# OpenSpindle_BASE.net
KiCad netlist of a schematic drawn in EAGLE
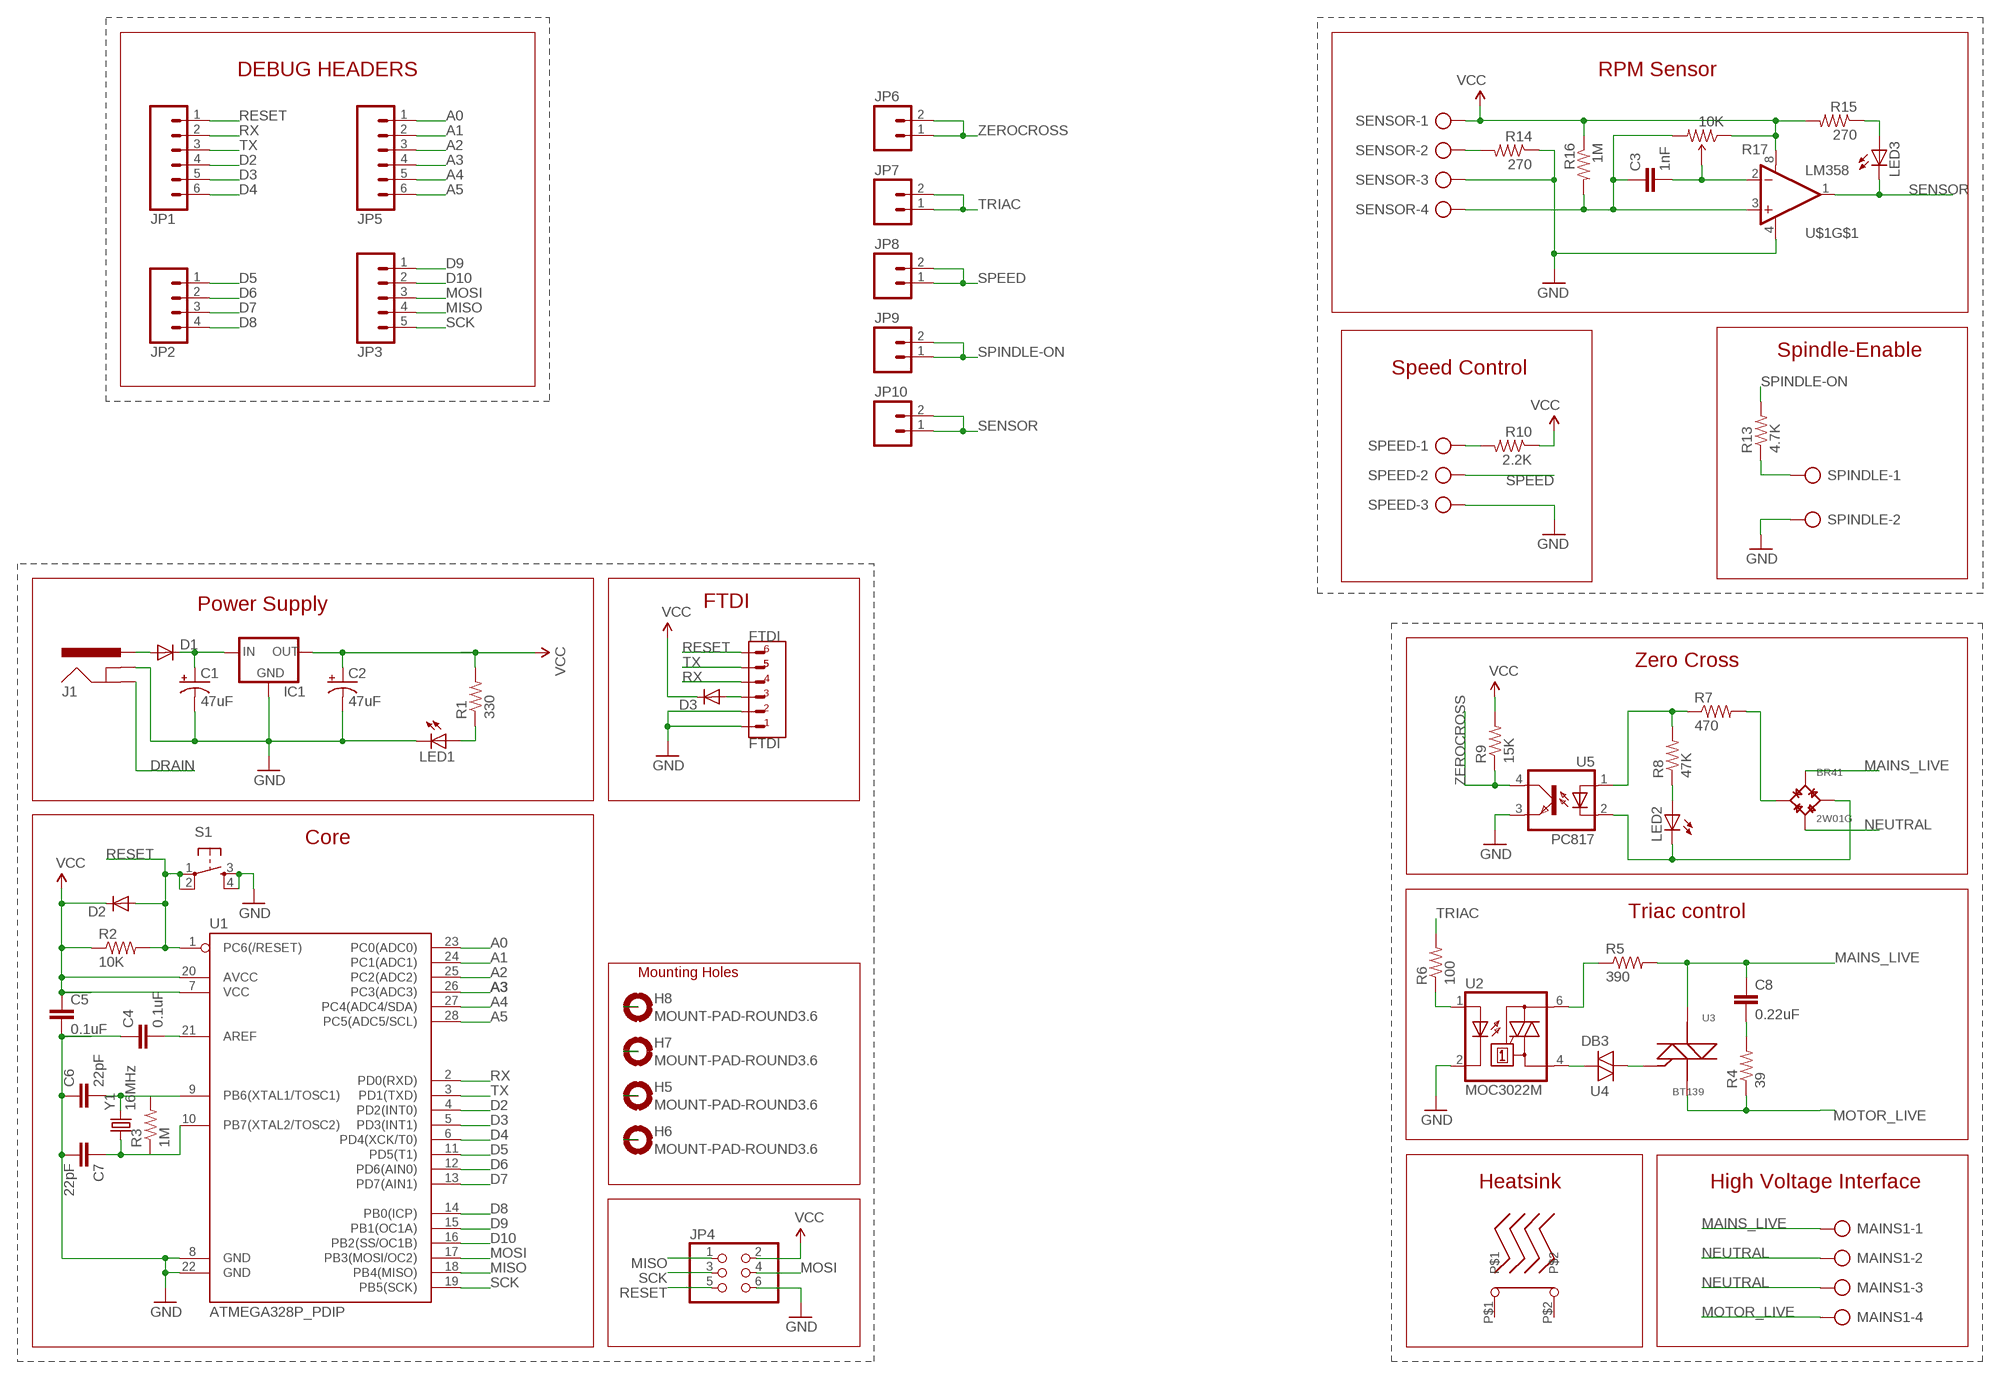
[diagram p0: schematic, sheet 1]

(export (version "E")
  (design (tool "Eeschema 10.0.6"))
  (components
    (comp (ref "BR41")
      (value "2W01G")
      (footprint "eagle-import:DIODEBRIDGE")
      (libsource (lib "eagle-import") (part "DIODEBRIDGE"))
    )
    (comp (ref "C1")
      (value "47uF")
      (footprint "eagle-import:CPOL-RADIAL-10UF-25V")
      (libsource (lib "eagle-import") (part "CAP_POLPTH2"))
    )
    (comp (ref "C2")
      (value "47uF")
      (footprint "eagle-import:CPOL-RADIAL-10UF-25V")
      (libsource (lib "eagle-import") (part "CAP_POLPTH2"))
    )
    (comp (ref "C3")
      (value "1nF")
      (footprint "eagle-import:CAP-PTH-SMALL")
      (libsource (lib "eagle-import") (part "SparkFun-Capacitors_CAPPTH"))
    )
    (comp (ref "C4")
      (value "0.1uF")
      (footprint "eagle-import:CAP-PTH-SMALL")
      (libsource (lib "eagle-import") (part "SparkFun-Capacitors_CAPPTH"))
    )
    (comp (ref "C5")
      (value "0.1uF")
      (footprint "eagle-import:CAP-PTH-SMALL")
      (libsource (lib "eagle-import") (part "SparkFun-Capacitors_CAPPTH"))
    )
    (comp (ref "C6")
      (value "22pF")
      (footprint "eagle-import:CAP-PTH-SMALL")
      (libsource (lib "eagle-import") (part "SparkFun-Capacitors_CAPPTH"))
    )
    (comp (ref "C7")
      (value "22pF")
      (footprint "eagle-import:CAP-PTH-SMALL")
      (libsource (lib "eagle-import") (part "SparkFun-Capacitors_CAPPTH"))
    )
    (comp (ref "C8")
      (value "0.22uF")
      (footprint "eagle-import:CAP-PTH-SMALL")
      (libsource (lib "eagle-import") (part "CAPPTH"))
    )
    (comp (ref "D1")
      (value "DIODEPTH")
      (footprint "eagle-import:DIODE-1N4001")
      (libsource (lib "eagle-import") (part "DIODEPTH"))
    )
    (comp (ref "D2")
      (value "DIODEPTH")
      (footprint "eagle-import:DIODE-1N4001")
      (libsource (lib "eagle-import") (part "DIODEPTH"))
    )
    (comp (ref "D3")
      (value "DIODEPTH")
      (footprint "eagle-import:DIODE-1N4001")
      (libsource (lib "eagle-import") (part "DIODEPTH"))
    )
    (comp (ref "FTDI")
      (value "FTDI")
      (footprint "eagle-import:6PINHEADER")
      (libsource (lib "eagle-import") (part "6PINHEADER0.1{dblquote}"))
    )
    (comp (ref "H5")
      (value "MOUNT-PAD-ROUND3.6")
      (footprint "eagle-import:3,6-PAD")
      (libsource (lib "eagle-import") (part "MOUNT-PAD-ROUND3.6"))
    )
    (comp (ref "H6")
      (value "MOUNT-PAD-ROUND3.6")
      (footprint "eagle-import:3,6-PAD")
      (libsource (lib "eagle-import") (part "MOUNT-PAD-ROUND3.6"))
    )
    (comp (ref "H7")
      (value "MOUNT-PAD-ROUND3.6")
      (footprint "eagle-import:3,6-PAD")
      (libsource (lib "eagle-import") (part "MOUNT-PAD-ROUND3.6"))
    )
    (comp (ref "H8")
      (value "MOUNT-PAD-ROUND3.6")
      (footprint "eagle-import:3,6-PAD")
      (libsource (lib "eagle-import") (part "MOUNT-PAD-ROUND3.6"))
    )
    (comp (ref "IC1")
      (value "V_REG_78XX-TO-220")
      (footprint "eagle-import:TO-220-ALT")
      (libsource (lib "eagle-import") (part "V_REG_78XX-TO-220"))
    )
    (comp (ref "J1")
      (value "POWER_JACKPTH_LOCK")
      (footprint "eagle-import:POWER_JACK_PTH_LOCK")
      (libsource (lib "eagle-import") (part "POWER_JACKPTH_LOCK"))
    )
    (comp (ref "JP1")
      (value "M06LOCK")
      (footprint "eagle-import:1X06_LOCK")
      (libsource (lib "eagle-import") (part "M06LOCK"))
    )
    (comp (ref "JP2")
      (value "M04LOCK")
      (footprint "eagle-import:1X04_LOCK")
      (libsource (lib "eagle-import") (part "M04LOCK"))
    )
    (comp (ref "JP3")
      (value "M05LOCK")
      (footprint "eagle-import:1X05_LOCK")
      (libsource (lib "eagle-import") (part "M05LOCK"))
    )
    (comp (ref "JP4")
      (value "PINHD-2X3")
      (footprint "eagle-import:2X03")
      (libsource (lib "eagle-import") (part "PINHD-2X3"))
    )
    (comp (ref "JP5")
      (value "M06LOCK")
      (footprint "eagle-import:1X06_LOCK")
      (libsource (lib "eagle-import") (part "M06LOCK"))
    )
    (comp (ref "JP6")
      (value "M02LOCK")
      (footprint "eagle-import:1X02_LOCK")
      (libsource (lib "eagle-import") (part "M02LOCK"))
    )
    (comp (ref "JP7")
      (value "M02LOCK")
      (footprint "eagle-import:1X02_LOCK")
      (libsource (lib "eagle-import") (part "M02LOCK"))
    )
    (comp (ref "JP8")
      (value "M02LOCK")
      (footprint "eagle-import:1X02_LOCK")
      (libsource (lib "eagle-import") (part "M02LOCK"))
    )
    (comp (ref "JP9")
      (value "M02LOCK")
      (footprint "eagle-import:1X02_LOCK")
      (libsource (lib "eagle-import") (part "M02LOCK"))
    )
    (comp (ref "JP10")
      (value "M02LOCK")
      (footprint "eagle-import:1X02_LOCK")
      (libsource (lib "eagle-import") (part "M02LOCK"))
    )
    (comp (ref "LED1")
      (value "LED5MM")
      (footprint "eagle-import:LED5MM")
      (libsource (lib "eagle-import") (part "adafruit2012_LED5MM"))
    )
    (comp (ref "LED2")
      (value "LED5MM")
      (footprint "eagle-import:LED5MM")
      (libsource (lib "eagle-import") (part "LED5MM"))
    )
    (comp (ref "LED3")
      (value "LED5MM")
      (footprint "eagle-import:LED5MM")
      (libsource (lib "eagle-import") (part "adafruit2012_LED5MM"))
    )
    (comp (ref "MAINS1")
      (value "AK500/4")
      (footprint "eagle-import:AK500_4")
      (libsource (lib "eagle-import") (part "AK500/4"))
    )
    (comp (ref "R1")
      (value "330")
      (footprint "eagle-import:AXIAL-0.3")
      (libsource (lib "eagle-import") (part "RESISTORAXIAL-0.3"))
    )
    (comp (ref "R2")
      (value "10K")
      (footprint "eagle-import:AXIAL-0.3")
      (libsource (lib "eagle-import") (part "RESISTORAXIAL-0.3"))
    )
    (comp (ref "R3")
      (value "1M")
      (footprint "eagle-import:AXIAL-0.3")
      (libsource (lib "eagle-import") (part "RESISTORAXIAL-0.3"))
    )
    (comp (ref "R4")
      (value "39")
      (footprint "eagle-import:AXIAL-0.3")
      (libsource (lib "eagle-import") (part "RESISTORAXIAL-0.3"))
    )
    (comp (ref "R5")
      (value "390")
      (footprint "eagle-import:AXIAL-0.3")
      (libsource (lib "eagle-import") (part "RESISTORAXIAL-0.3"))
    )
    (comp (ref "R6")
      (value "100")
      (footprint "eagle-import:AXIAL-0.3")
      (libsource (lib "eagle-import") (part "RESISTORAXIAL-0.3"))
    )
    (comp (ref "R7")
      (value "470")
      (footprint "eagle-import:SQM_5-10")
      (libsource (lib "eagle-import") (part "RESISTORM_5-10"))
    )
    (comp (ref "R8")
      (value "47K")
      (footprint "eagle-import:SQM_5-10")
      (libsource (lib "eagle-import") (part "RESISTORM_5-10"))
    )
    (comp (ref "R9")
      (value "15K")
      (footprint "eagle-import:AXIAL-0.3")
      (libsource (lib "eagle-import") (part "RESISTORAXIAL-0.3"))
    )
    (comp (ref "R10")
      (value "2.2K")
      (footprint "eagle-import:AXIAL-0.3")
      (libsource (lib "eagle-import") (part "RESISTORAXIAL-0.3"))
    )
    (comp (ref "R13")
      (value "4.7K")
      (footprint "eagle-import:AXIAL-0.3")
      (libsource (lib "eagle-import") (part "RESISTORAXIAL-0.3"))
    )
    (comp (ref "R14")
      (value "270")
      (footprint "eagle-import:AXIAL-0.3")
      (libsource (lib "eagle-import") (part "RESISTORAXIAL-0.3"))
    )
    (comp (ref "R15")
      (value "270")
      (footprint "eagle-import:AXIAL-0.3")
      (libsource (lib "eagle-import") (part "RESISTORAXIAL-0.3"))
    )
    (comp (ref "R16")
      (value "1M")
      (footprint "eagle-import:AXIAL-0.3")
      (libsource (lib "eagle-import") (part "RESISTORAXIAL-0.3"))
    )
    (comp (ref "R17")
      (value "10K")
      (footprint "eagle-import:TRIMPOT_PTH_S3_LOCK")
      (libsource (lib "eagle-import") (part "TRIMPOTTRIMPOT_PTH_S3_LOCK"))
    )
    (comp (ref "S1")
      (value "TAC_SWITCHPTH")
      (footprint "eagle-import:TACTILE-PTH")
      (libsource (lib "eagle-import") (part "TAC_SWITCHPTH"))
    )
    (comp (ref "SENSOR")
      (value "AK500/4")
      (footprint "eagle-import:AK500_4")
      (libsource (lib "eagle-import") (part "AK500/4"))
    )
    (comp (ref "SPEED")
      (value "AK500/3")
      (footprint "eagle-import:AK500_3")
      (libsource (lib "eagle-import") (part "AK500/3"))
    )
    (comp (ref "SPINDLE")
      (value "AK500/2")
      (footprint "eagle-import:AK500_2")
      (libsource (lib "eagle-import") (part "AK500/2"))
    )
    (comp (ref "U$1")
      (value "LM358")
      (footprint "eagle-import:DIP08")
      (libsource (lib "eagle-import") (part "LM358"))
    )
    (comp (ref "U$2")
      (value "HEATSINK529802B02500G")
      (footprint "eagle-import:529802B02500G")
      (libsource (lib "eagle-import") (part "HEATSINK529802B02500G"))
    )
    (comp (ref "U1")
      (value "ATMEGA328P_PDIP")
      (footprint "eagle-import:DIL28-3")
      (libsource (lib "eagle-import") (part "ATMEGA328P_PDIP"))
    )
    (comp (ref "U2")
      (value "MOC3022M")
      (footprint "eagle-import:DIL06")
      (fields (field (name "MF") "FAIRCHILD SEMICONDUCTOR") (field (name "MPN") "MOC3022-M"))
      (libsource (lib "eagle-import") (part "MOC30M22"))
    )
    (comp (ref "U3")
      (value "BT139")
      (footprint "eagle-import:TRIAC")
      (libsource (lib "eagle-import") (part "TRIAC"))
    )
    (comp (ref "U4")
      (value "DB3")
      (footprint "eagle-import:DO35-10")
      (libsource (lib "eagle-import") (part "DIAC-DO35-10"))
    )
    (comp (ref "U5")
      (value "PC817")
      (footprint "eagle-import:DIL04")
      (fields (field (name "MPN") "PC817X4J000F"))
      (libsource (lib "eagle-import") (part "PC817"))
    )
    (comp (ref "Y1")
      (value "16MHz")
      (footprint "eagle-import:HC49U-V")
      (libsource (lib "eagle-import") (part "CRYSTALHC49UV"))
    )
  )
  (nets
    (net (code "1") (name "/A0") (class "Default")
      (node (ref "JP5") (pin "1") (pinfunction "1_1") (pintype "passive"))
      (node (ref "U1") (pin "23") (pinfunction "PC0(ADC0)_23") (pintype "bidirectional"))
    )
    (net (code "2") (name "/A1") (class "Default")
      (node (ref "JP5") (pin "2") (pinfunction "2_2") (pintype "passive"))
      (node (ref "U1") (pin "24") (pinfunction "PC1(ADC1)_24") (pintype "bidirectional"))
    )
    (net (code "3") (name "/A2") (class "Default")
      (node (ref "JP5") (pin "3") (pinfunction "3_3") (pintype "passive"))
      (node (ref "U1") (pin "25") (pinfunction "PC2(ADC2)_25") (pintype "bidirectional"))
    )
    (net (code "4") (name "/A3") (class "Default")
      (node (ref "JP5") (pin "4") (pinfunction "4_4") (pintype "passive"))
      (node (ref "U1") (pin "26") (pinfunction "PC3(ADC3)_26") (pintype "bidirectional"))
    )
    (net (code "5") (name "/A4") (class "Default")
      (node (ref "JP5") (pin "5") (pinfunction "5_5") (pintype "passive"))
      (node (ref "U1") (pin "27") (pinfunction "PC4(ADC4/SDA)_27") (pintype "bidirectional"))
    )
    (net (code "6") (name "/A5") (class "Default")
      (node (ref "JP5") (pin "6") (pinfunction "6_6") (pintype "passive"))
      (node (ref "U1") (pin "28") (pinfunction "PC5(ADC5/SCL)_28") (pintype "bidirectional"))
    )
    (net (code "7") (name "/D2") (class "Default")
      (node (ref "JP1") (pin "4") (pinfunction "4_4") (pintype "passive"))
      (node (ref "U1") (pin "4") (pinfunction "PD2(INT0)_4") (pintype "bidirectional"))
    )
    (net (code "8") (name "/D3") (class "Default")
      (node (ref "JP1") (pin "5") (pinfunction "5_5") (pintype "passive"))
      (node (ref "U1") (pin "5") (pinfunction "PD3(INT1)_5") (pintype "bidirectional"))
    )
    (net (code "9") (name "/D4") (class "Default")
      (node (ref "JP1") (pin "6") (pinfunction "6_6") (pintype "passive"))
      (node (ref "U1") (pin "6") (pinfunction "PD4(XCK/T0)_6") (pintype "bidirectional"))
    )
    (net (code "10") (name "/D5") (class "Default")
      (node (ref "JP2") (pin "1") (pinfunction "1_1") (pintype "passive"))
      (node (ref "U1") (pin "11") (pinfunction "PD5(T1)_11") (pintype "bidirectional"))
    )
    (net (code "11") (name "/D6") (class "Default")
      (node (ref "JP2") (pin "2") (pinfunction "2_2") (pintype "passive"))
      (node (ref "U1") (pin "12") (pinfunction "PD6(AIN0)_12") (pintype "bidirectional"))
    )
    (net (code "12") (name "/D7") (class "Default")
      (node (ref "JP2") (pin "3") (pinfunction "3_3") (pintype "passive"))
      (node (ref "U1") (pin "13") (pinfunction "PD7(AIN1)_13") (pintype "bidirectional"))
    )
    (net (code "13") (name "/D8") (class "Default")
      (node (ref "JP2") (pin "4") (pinfunction "4_4") (pintype "passive"))
      (node (ref "U1") (pin "14") (pinfunction "PB0(ICP)_14") (pintype "bidirectional"))
    )
    (net (code "14") (name "/D9") (class "Default")
      (node (ref "JP3") (pin "1") (pinfunction "1_1") (pintype "passive"))
      (node (ref "U1") (pin "15") (pinfunction "PB1(OC1A)_15") (pintype "bidirectional"))
    )
    (net (code "15") (name "/D10") (class "Default")
      (node (ref "JP3") (pin "2") (pinfunction "2_2") (pintype "passive"))
      (node (ref "U1") (pin "16") (pinfunction "PB2(SS/OC1B)_16") (pintype "bidirectional"))
    )
    (net (code "16") (name "/DRAIN") (class "Default")
      (node (ref "J1") (pin "GND") (pinfunction "GND_GND") (pintype "bidirectional"))
    )
    (net (code "17") (name "/MAINS_LIVE") (class "Default")
      (node (ref "BR41") (pin "AC1") (pinfunction "AC1_AC1") (pintype "bidirectional"))
      (node (ref "C8") (pin "1") (pinfunction "1_1") (pintype "passive"))
      (node (ref "MAINS1") (pin "1") (pinfunction "KL_1") (pintype "passive"))
      (node (ref "R5") (pin "P$2") (pinfunction "2_P$2") (pintype "passive"))
      (node (ref "U3") (pin "2") (pinfunction "A_2") (pintype "bidirectional"))
    )
    (net (code "18") (name "/MISO") (class "Default")
      (node (ref "JP3") (pin "4") (pinfunction "4_4") (pintype "passive"))
      (node (ref "JP4") (pin "1") (pinfunction "1_1") (pintype "passive"))
      (node (ref "U1") (pin "18") (pinfunction "PB4(MISO)_18") (pintype "bidirectional"))
    )
    (net (code "19") (name "/MOSI") (class "Default")
      (node (ref "JP3") (pin "3") (pinfunction "3_3") (pintype "passive"))
      (node (ref "JP4") (pin "4") (pinfunction "4_4") (pintype "passive"))
      (node (ref "U1") (pin "17") (pinfunction "PB3(MOSI/OC2)_17") (pintype "bidirectional"))
    )
    (net (code "20") (name "/MOTOR_LIVE") (class "Default")
      (node (ref "MAINS1") (pin "4") (pinfunction "KL_4") (pintype "passive"))
      (node (ref "R4") (pin "P$1") (pinfunction "1_P$1") (pintype "passive"))
      (node (ref "U3") (pin "3") (pinfunction "C_3") (pintype "bidirectional"))
    )
    (net (code "21") (name "/NEUTRAL") (class "Default")
      (node (ref "BR41") (pin "AC2") (pinfunction "AC2_AC2") (pintype "bidirectional"))
      (node (ref "MAINS1") (pin "2") (pinfunction "KL_2") (pintype "passive"))
      (node (ref "MAINS1") (pin "3") (pinfunction "KL_3") (pintype "passive"))
    )
    (net (code "22") (name "/P$1") (class "Default")
      (node (ref "U$2") (pin "P$1") (pinfunction "P$1_P$1") (pintype "power_in"))
    )
    (net (code "23") (name "/P$2") (class "Default")
      (node (ref "U$2") (pin "P$2") (pinfunction "P$2_P$2") (pintype "power_in"))
    )
    (net (code "24") (name "/RESET") (class "Default")
      (node (ref "D2") (pin "A") (pinfunction "A_A") (pintype "passive"))
      (node (ref "FTDI") (pin "P$6") (pinfunction "P$6_P$6") (pintype "bidirectional"))
      (node (ref "JP1") (pin "1") (pinfunction "1_1") (pintype "passive"))
      (node (ref "JP4") (pin "5") (pinfunction "5_5") (pintype "passive"))
      (node (ref "R2") (pin "P$2") (pinfunction "2_P$2") (pintype "passive"))
      (node (ref "S1") (pin "1") (pinfunction "1_1") (pintype "passive"))
      (node (ref "S1") (pin "2") (pinfunction "2_2") (pintype "passive"))
      (node (ref "U1") (pin "1") (pinfunction "PC6(/RESET)_1") (pintype "bidirectional"))
    )
    (net (code "25") (name "/RX") (class "Default")
      (node (ref "FTDI") (pin "P$4") (pinfunction "P$4_P$4") (pintype "bidirectional"))
      (node (ref "JP1") (pin "2") (pinfunction "2_2") (pintype "passive"))
      (node (ref "U1") (pin "2") (pinfunction "PD0(RXD)_2") (pintype "bidirectional"))
    )
    (net (code "26") (name "/SCK") (class "Default")
      (node (ref "JP3") (pin "5") (pinfunction "5_5") (pintype "passive"))
      (node (ref "JP4") (pin "3") (pinfunction "3_3") (pintype "passive"))
      (node (ref "U1") (pin "19") (pinfunction "PB5(SCK)_19") (pintype "bidirectional"))
    )
    (net (code "27") (name "/SENSOR") (class "Default")
      (node (ref "JP10") (pin "1") (pinfunction "1_1") (pintype "passive"))
      (node (ref "JP10") (pin "2") (pinfunction "2_2") (pintype "passive"))
      (node (ref "LED3") (pin "K") (pinfunction "C_K") (pintype "passive"))
      (node (ref "U$1") (pin "1") (pinfunction "OUT_1") (pintype "output"))
    )
    (net (code "28") (name "/SPEED") (class "Default")
      (node (ref "JP8") (pin "1") (pinfunction "1_1") (pintype "passive"))
      (node (ref "JP8") (pin "2") (pinfunction "2_2") (pintype "passive"))
      (node (ref "SPEED") (pin "2") (pinfunction "KL_2") (pintype "passive"))
    )
    (net (code "29") (name "/SPINDLE-ON") (class "Default")
      (node (ref "JP9") (pin "1") (pinfunction "1_1") (pintype "passive"))
      (node (ref "JP9") (pin "2") (pinfunction "2_2") (pintype "passive"))
      (node (ref "R13") (pin "P$2") (pinfunction "2_P$2") (pintype "passive"))
    )
    (net (code "30") (name "/TRIAC") (class "Default")
      (node (ref "JP7") (pin "1") (pinfunction "1_1") (pintype "passive"))
      (node (ref "JP7") (pin "2") (pinfunction "2_2") (pintype "passive"))
      (node (ref "R6") (pin "P$2") (pinfunction "2_P$2") (pintype "passive"))
    )
    (net (code "31") (name "/TX") (class "Default")
      (node (ref "FTDI") (pin "P$5") (pinfunction "P$5_P$5") (pintype "bidirectional"))
      (node (ref "JP1") (pin "3") (pinfunction "3_3") (pintype "passive"))
      (node (ref "U1") (pin "3") (pinfunction "PD1(TXD)_3") (pintype "bidirectional"))
    )
    (net (code "32") (name "/ZEROCROSS") (class "Default")
      (node (ref "JP6") (pin "1") (pinfunction "1_1") (pintype "passive"))
      (node (ref "JP6") (pin "2") (pinfunction "2_2") (pintype "passive"))
      (node (ref "R9") (pin "P$1") (pinfunction "1_P$1") (pintype "passive"))
      (node (ref "U5") (pin "4") (pinfunction "COL_4") (pintype "passive"))
    )
    (net (code "33") (name "GND") (class "Default")
      (node (ref "C1") (pin "2") (pinfunction "-_2") (pintype "passive"))
      (node (ref "C2") (pin "2") (pinfunction "-_2") (pintype "passive"))
      (node (ref "C4") (pin "1") (pinfunction "1_1") (pintype "passive"))
      (node (ref "C5") (pin "2") (pinfunction "2_2") (pintype "passive"))
      (node (ref "C6") (pin "1") (pinfunction "1_1") (pintype "passive"))
      (node (ref "C7") (pin "2") (pinfunction "2_2") (pintype "passive"))
      (node (ref "FTDI") (pin "P$1") (pinfunction "P$1_P$1") (pintype "bidirectional"))
      (node (ref "FTDI") (pin "P$2") (pinfunction "P$2_P$2") (pintype "bidirectional"))
      (node (ref "IC1") (pin "GND") (pinfunction "GND_GND") (pintype "input"))
      (node (ref "J1") (pin "GNDBREAK") (pinfunction "GNDBREAK_GNDBREAK") (pintype "bidirectional"))
      (node (ref "JP4") (pin "6") (pinfunction "6_6") (pintype "passive"))
      (node (ref "LED1") (pin "K") (pinfunction "C_K") (pintype "passive"))
      (node (ref "R14") (pin "P$1") (pinfunction "1_P$1") (pintype "passive"))
      (node (ref "S1") (pin "3") (pinfunction "3_3") (pintype "passive"))
      (node (ref "S1") (pin "4") (pinfunction "4_4") (pintype "passive"))
      (node (ref "SENSOR") (pin "3") (pinfunction "KL_3") (pintype "passive"))
      (node (ref "SPEED") (pin "3") (pinfunction "KL_3") (pintype "passive"))
      (node (ref "SPINDLE") (pin "2") (pinfunction "KL_2") (pintype "passive"))
      (node (ref "U$1") (pin "4") (pinfunction "V-_4") (pintype "power_in"))
      (node (ref "U1") (pin "22") (pinfunction "GND_22") (pintype "bidirectional"))
      (node (ref "U1") (pin "8") (pinfunction "GND_8") (pintype "bidirectional"))
      (node (ref "U2") (pin "2") (pinfunction "C_2") (pintype "passive"))
      (node (ref "U5") (pin "3") (pinfunction "EMIT_3") (pintype "passive"))
    )
    (net (code "34") (name "Net-(C1-+)") (class "Default")
      (node (ref "C1") (pin "1") (pinfunction "+_1") (pintype "passive"))
      (node (ref "D1") (pin "C") (pinfunction "C_C") (pintype "passive"))
      (node (ref "IC1") (pin "IN") (pinfunction "IN_IN") (pintype "input"))
    )
    (net (code "35") (name "Net-(D1-PadA)") (class "Default")
      (node (ref "D1") (pin "A") (pinfunction "A_A") (pintype "passive"))
      (node (ref "J1") (pin "PWR") (pinfunction "PWR_PWR") (pintype "bidirectional"))
    )
    (net (code "36") (name "Net-(D3-PadA)") (class "Default")
      (node (ref "D3") (pin "A") (pinfunction "A_A") (pintype "passive"))
      (node (ref "FTDI") (pin "P$3") (pinfunction "P$3_P$3") (pintype "bidirectional"))
    )
    (net (code "37") (name "Net-(LED2-C)") (class "Default")
      (node (ref "BR41") (pin "-") (pinfunction "-_-") (pintype "bidirectional"))
      (node (ref "LED2") (pin "K") (pinfunction "C_K") (pintype "passive"))
      (node (ref "U5") (pin "2") (pinfunction "C_2") (pintype "passive"))
    )
    (net (code "38") (name "Net-(R1-1)") (class "Default")
      (node (ref "LED1") (pin "A") (pinfunction "A_A") (pintype "passive"))
      (node (ref "R1") (pin "P$1") (pinfunction "1_P$1") (pintype "passive"))
    )
    (net (code "39") (name "Net-(R3-1)") (class "Default")
      (node (ref "C7") (pin "1") (pinfunction "1_1") (pintype "passive"))
      (node (ref "R3") (pin "P$1") (pinfunction "1_P$1") (pintype "passive"))
      (node (ref "U1") (pin "10") (pinfunction "PB7(XTAL2/TOSC2)_10") (pintype "bidirectional"))
      (node (ref "Y1") (pin "1") (pinfunction "1_1") (pintype "passive"))
    )
    (net (code "40") (name "Net-(R3-2)") (class "Default")
      (node (ref "C6") (pin "2") (pinfunction "2_2") (pintype "passive"))
      (node (ref "R3") (pin "P$2") (pinfunction "2_P$2") (pintype "passive"))
      (node (ref "U1") (pin "9") (pinfunction "PB6(XTAL1/TOSC1)_9") (pintype "bidirectional"))
      (node (ref "Y1") (pin "2") (pinfunction "2_2") (pintype "passive"))
    )
    (net (code "41") (name "Net-(R4-2)") (class "Default")
      (node (ref "C8") (pin "2") (pinfunction "2_2") (pintype "passive"))
      (node (ref "R4") (pin "P$2") (pinfunction "2_P$2") (pintype "passive"))
    )
    (net (code "42") (name "Net-(R5-1)") (class "Default")
      (node (ref "R5") (pin "P$1") (pinfunction "1_P$1") (pintype "passive"))
      (node (ref "U2") (pin "6") (pinfunction "A2_6") (pintype "passive"))
    )
    (net (code "43") (name "Net-(R6-1)") (class "Default")
      (node (ref "R6") (pin "P$1") (pinfunction "1_P$1") (pintype "passive"))
      (node (ref "U2") (pin "1") (pinfunction "A_1") (pintype "passive"))
    )
    (net (code "44") (name "Net-(R7-1)") (class "Default")
      (node (ref "R7") (pin "P1") (pinfunction "1_P1") (pintype "passive"))
      (node (ref "R8") (pin "P2") (pinfunction "2_P2") (pintype "passive"))
      (node (ref "U5") (pin "1") (pinfunction "A_1") (pintype "passive"))
    )
    (net (code "45") (name "Net-(R7-2)") (class "Default")
      (node (ref "BR41") (pin "+") (pinfunction "+_+") (pintype "bidirectional"))
      (node (ref "R7") (pin "P2") (pinfunction "2_P2") (pintype "passive"))
    )
    (net (code "46") (name "Net-(R8-1)") (class "Default")
      (node (ref "LED2") (pin "A") (pinfunction "A_A") (pintype "passive"))
      (node (ref "R8") (pin "P1") (pinfunction "1_P1") (pintype "passive"))
    )
    (net (code "47") (name "Net-(R10-2)") (class "Default")
      (node (ref "R10") (pin "P$2") (pinfunction "2_P$2") (pintype "passive"))
      (node (ref "SPEED") (pin "1") (pinfunction "KL_1") (pintype "passive"))
    )
    (net (code "48") (name "Net-(R13-1)") (class "Default")
      (node (ref "R13") (pin "P$1") (pinfunction "1_P$1") (pintype "passive"))
      (node (ref "SPINDLE") (pin "1") (pinfunction "KL_1") (pintype "passive"))
    )
    (net (code "49") (name "Net-(R14-2)") (class "Default")
      (node (ref "R14") (pin "P$2") (pinfunction "2_P$2") (pintype "passive"))
      (node (ref "SENSOR") (pin "2") (pinfunction "KL_2") (pintype "passive"))
    )
    (net (code "50") (name "Net-(R15-1)") (class "Default")
      (node (ref "LED3") (pin "A") (pinfunction "A_A") (pintype "passive"))
      (node (ref "R15") (pin "P$1") (pinfunction "1_P$1") (pintype "passive"))
    )
    (net (code "51") (name "Net-(R16-2)") (class "Default")
      (node (ref "C3") (pin "1") (pinfunction "1_1") (pintype "passive"))
      (node (ref "R16") (pin "P$2") (pinfunction "2_P$2") (pintype "passive"))
      (node (ref "R17") (pin "3") (pinfunction "CW_3") (pintype "passive"))
      (node (ref "SENSOR") (pin "4") (pinfunction "KL_4") (pintype "passive"))
      (node (ref "U$1") (pin "3") (pinfunction "+IN_3") (pintype "input"))
    )
    (net (code "52") (name "Net-(R17-WIPER)") (class "Default")
      (node (ref "C3") (pin "2") (pinfunction "2_2") (pintype "passive"))
      (node (ref "R17") (pin "2") (pinfunction "WIPER_2") (pintype "passive"))
      (node (ref "U$1") (pin "2") (pinfunction "-IN_2") (pintype "input"))
    )
    (net (code "53") (name "Net-(U1-AREF)") (class "Default")
      (node (ref "C4") (pin "2") (pinfunction "2_2") (pintype "passive"))
      (node (ref "U1") (pin "21") (pinfunction "AREF_21") (pintype "bidirectional"))
    )
    (net (code "54") (name "Net-(U2-A1)") (class "Default")
      (node (ref "U2") (pin "4") (pinfunction "A1_4") (pintype "passive"))
      (node (ref "U4") (pin "C") (pinfunction "2_C") (pintype "passive"))
    )
    (net (code "55") (name "Net-(U3-B)") (class "Default")
      (node (ref "U3") (pin "1") (pinfunction "B_1") (pintype "bidirectional"))
      (node (ref "U4") (pin "A") (pinfunction "1_A") (pintype "passive"))
    )
    (net (code "56") (name "VCC") (class "Default")
      (node (ref "C2") (pin "1") (pinfunction "+_1") (pintype "passive"))
      (node (ref "C5") (pin "1") (pinfunction "1_1") (pintype "passive"))
      (node (ref "D2") (pin "C") (pinfunction "C_C") (pintype "passive"))
      (node (ref "D3") (pin "C") (pinfunction "C_C") (pintype "passive"))
      (node (ref "IC1") (pin "OUT") (pinfunction "OUT_OUT") (pintype "output"))
      (node (ref "JP4") (pin "2") (pinfunction "2_2") (pintype "passive"))
      (node (ref "R1") (pin "P$2") (pinfunction "2_P$2") (pintype "passive"))
      (node (ref "R10") (pin "P$1") (pinfunction "1_P$1") (pintype "passive"))
      (node (ref "R15") (pin "P$2") (pinfunction "2_P$2") (pintype "passive"))
      (node (ref "R16") (pin "P$1") (pinfunction "1_P$1") (pintype "passive"))
      (node (ref "R17") (pin "1") (pinfunction "CCW_1") (pintype "passive"))
      (node (ref "R2") (pin "P$1") (pinfunction "1_P$1") (pintype "passive"))
      (node (ref "R9") (pin "P$2") (pinfunction "2_P$2") (pintype "passive"))
      (node (ref "SENSOR") (pin "1") (pinfunction "KL_1") (pintype "passive"))
      (node (ref "U$1") (pin "8") (pinfunction "V+_8") (pintype "power_in"))
      (node (ref "U1") (pin "20") (pinfunction "AVCC_20") (pintype "bidirectional"))
      (node (ref "U1") (pin "7") (pinfunction "VCC_7") (pintype "bidirectional"))
    )
    (net (code "57") (name "unconnected-(H5-MOUNT-PadB3,6)") (class "Default")
      (node (ref "H5") (pin "B3,6") (pinfunction "MOUNT_B3,6") (pintype "passive"))
    )
    (net (code "58") (name "unconnected-(H6-MOUNT-PadB3,6)") (class "Default")
      (node (ref "H6") (pin "B3,6") (pinfunction "MOUNT_B3,6") (pintype "passive"))
    )
    (net (code "59") (name "unconnected-(H7-MOUNT-PadB3,6)") (class "Default")
      (node (ref "H7") (pin "B3,6") (pinfunction "MOUNT_B3,6") (pintype "passive"))
    )
    (net (code "60") (name "unconnected-(H8-MOUNT-PadB3,6)") (class "Default")
      (node (ref "H8") (pin "B3,6") (pinfunction "MOUNT_B3,6") (pintype "passive"))
    )
  )
)
